# STM32_min.net
KiCad netlist of a schematic drawn in Altium Designer
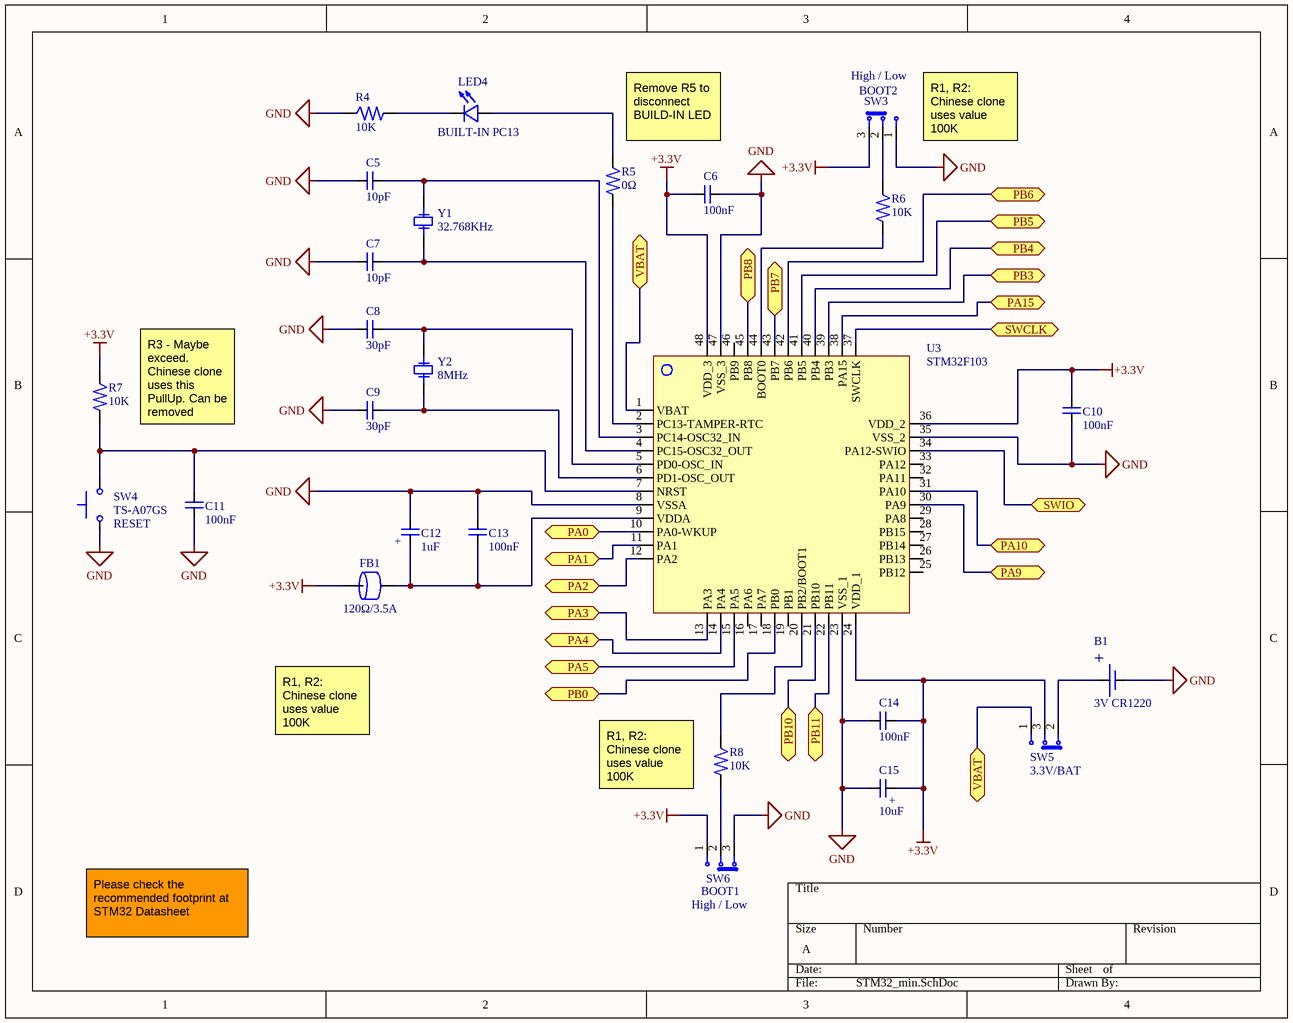
[diagram p0: STM32_min.SchDoc]

(export (version "E")
  (design (tool "Eeschema 10.0.6"))
  (components
    (comp (ref "B1")
      (value "3V CR1220")
      (footprint "THT_BH-25T-GLD")
      (description "Battery Holder for CR-2032 Type Battery BH-25T-GLD")
      (libsource (lib "THT_BH-25T-GLD") (part "THT_BH-25T-GLD"))
    )
    (comp (ref "C5")
      (value "10pF")
      (footprint "SMT_CAP_CER_MODEL_0805(2012)_SAMSUNG")
      (description "SMT SAMSUNG Ceramic Capacitor MODEL *V *pF 0805(2012) CL21C100DBANNNC(etc.)")
      (libsource (lib "SMT_CAP_CER_MODEL_0805(2012)_SAMSUNG") (part "SMT_CAP_CER_MODEL_0805(2012)_SAMSUNG"))
    )
    (comp (ref "C6")
      (value "100nF")
      (footprint "SMT_CAP_MODEL_1206(3216)_SAMSUNG")
      (description "SMT Samsung Ceramic Capacitor MODEL *V *nF 1206(3216)  CL31B104KBCNNNC(etc.)")
      (libsource (lib "SMT_CAP_MODEL_1206(3216)_SAMSUNG") (part "SMT_CAP_MODEL_1206(3216)_SAMSUNG"))
    )
    (comp (ref "C7")
      (value "10pF")
      (footprint "SMT_CAP_CER_MODEL_0805(2012)_SAMSUNG")
      (description "SMT SAMSUNG Ceramic Capacitor MODEL *V *pF 0805(2012) CL21C100DBANNNC(etc.)")
      (libsource (lib "SMT_CAP_CER_MODEL_0805(2012)_SAMSUNG") (part "SMT_CAP_CER_MODEL_0805(2012)_SAMSUNG"))
    )
    (comp (ref "C8")
      (value "30pF")
      (footprint "SMT_CAP_MODEL_1206(3216)_SAMSUNG")
      (description "SMT Samsung Ceramic Capacitor MODEL *V *nF 1206(3216)  CL31B104KBCNNNC(etc.)")
      (libsource (lib "SMT_CAP_MODEL_1206(3216)_SAMSUNG") (part "SMT_CAP_MODEL_1206(3216)_SAMSUNG"))
    )
    (comp (ref "C9")
      (value "30pF")
      (footprint "SMT_CAP_MODEL_1206(3216)_SAMSUNG")
      (description "SMT Samsung Ceramic Capacitor MODEL *V *nF 1206(3216)  CL31B104KBCNNNC(etc.)")
      (libsource (lib "SMT_CAP_MODEL_1206(3216)_SAMSUNG") (part "SMT_CAP_MODEL_1206(3216)_SAMSUNG"))
    )
    (comp (ref "C10")
      (value "100nF")
      (footprint "SMT_CAP_MODEL_1206(3216)_SAMSUNG")
      (description "SMT Samsung Ceramic Capacitor MODEL *V *nF 1206(3216)  CL31B104KBCNNNC(etc.)")
      (libsource (lib "SMT_CAP_MODEL_1206(3216)_SAMSUNG") (part "SMT_CAP_MODEL_1206(3216)_SAMSUNG"))
    )
    (comp (ref "C11")
      (value "100nF")
      (footprint "SMT_CAP_MODEL_1206(3216)_SAMSUNG")
      (description "SMT Samsung Ceramic Capacitor MODEL *V *nF 1206(3216)  CL31B104KBCNNNC(etc.)")
      (libsource (lib "SMT_CAP_MODEL_1206(3216)_SAMSUNG") (part "SMT_CAP_MODEL_1206(3216)_SAMSUNG"))
    )
    (comp (ref "C12")
      (value "1uF")
      (footprint "SMT_CAP_TANT_MODEL_1206(3216)_KYOCERA")
      (description "SMT KYOCERA Tantalum Capacitor MODEL *V *uF 1206(3216) EAN_3216-18 TAJA105M016RNJ(etc.)")
      (libsource (lib "SMT_CAP_TANT_MODEL_1206(3216)_KYOCERA") (part "SMT_CAP_TANT_MODEL_1206(3216)_KYOCERA"))
    )
    (comp (ref "C13")
      (value "100nF")
      (footprint "SMT_CAP_MODEL_1206(3216)_SAMSUNG")
      (description "SMT Samsung Ceramic Capacitor MODEL *V *nF 1206(3216)  CL31B104KBCNNNC(etc.)")
      (libsource (lib "SMT_CAP_MODEL_1206(3216)_SAMSUNG") (part "SMT_CAP_MODEL_1206(3216)_SAMSUNG"))
    )
    (comp (ref "C14")
      (value "100nF")
      (footprint "SMT_CAP_MODEL_1206(3216)_SAMSUNG")
      (description "SMT Samsung Ceramic Capacitor MODEL *V *nF 1206(3216)  CL31B104KBCNNNC(etc.)")
      (libsource (lib "SMT_CAP_MODEL_1206(3216)_SAMSUNG") (part "SMT_CAP_MODEL_1206(3216)_SAMSUNG"))
    )
    (comp (ref "C15")
      (value "10uF")
      (footprint "SMT_CAP_TANT_MODEL_1210(3528)_KYOCERA")
      (description "SMT KYOCERA Tantalum Capacitor MODEL *V *uF 1210(3528)  TAJB106K016RNJ(etc.)")
      (libsource (lib "SMT_CAP_TANT_MODEL_1210(3528)_KYOCERA") (part "SMT_CAP_TANT_MODEL_1210(3528)_KYOCERA"))
    )
    (comp (ref "FB1")
      (value "120Ω/3.5A")
      (footprint "SMT_FERR_BEAD_MODEL_1206(3216)_MURATA")
      (description "SMT MURATA Ferrite Bead MODEL 1206(3216) BLM31PG121SN1L *Ω/*mA")
      (libsource (lib "SMT_FERR_BEAD_MODEL_1206(3216)_MURATA") (part "SMT_FERR_BEAD_MODEL_1206(3216)_MURATA"))
    )
    (comp (ref "LED4")
      (value "BUILT-IN PC13")
      (footprint "DIOM2012X18N")
      (description "Led Diode 0805(2012) Cathode Mark, 20mA")
      (libsource (lib "SMT_LED_0805(2012)") (part "SMT_LED_0805(2012)"))
    )
    (comp (ref "R4")
      (value "10K")
      (footprint "SMT_RES_MODEL_1206(3216)_ROHM")
      (description "SMT ROHM Resistor MODEL 1206(3216) 1/4W MCR18ERTJ000")
      (libsource (lib "SMT_RES_MODEL_1206(3216)_ROHM") (part "SMT_RES_MODEL_1206(3216)_ROHM"))
    )
    (comp (ref "R5")
      (value "0Ω")
      (footprint "SMT_RES_MODEL_1206(3216)_ROHM")
      (description "SMT ROHM Resistor MODEL 1206(3216) 1/4W MCR18ERTJ000")
      (libsource (lib "SMT_RES_MODEL_1206(3216)_ROHM") (part "SMT_RES_MODEL_1206(3216)_ROHM"))
    )
    (comp (ref "R6")
      (value "10K")
      (footprint "SMT_RES_MODEL_1206(3216)_ROHM")
      (description "SMT ROHM Resistor MODEL 1206(3216) 1/4W MCR18ERTJ000")
      (libsource (lib "SMT_RES_MODEL_1206(3216)_ROHM") (part "SMT_RES_MODEL_1206(3216)_ROHM"))
    )
    (comp (ref "R7")
      (value "10K")
      (footprint "SMT_RES_MODEL_1206(3216)_ROHM")
      (description "SMT ROHM Resistor MODEL 1206(3216) 1/4W MCR18ERTJ000")
      (libsource (lib "SMT_RES_MODEL_1206(3216)_ROHM") (part "SMT_RES_MODEL_1206(3216)_ROHM"))
    )
    (comp (ref "R8")
      (value "10K")
      (footprint "SMT_RES_MODEL_1206(3216)_ROHM")
      (description "SMT ROHM Resistor MODEL 1206(3216) 1/4W MCR18ERTJ000")
      (libsource (lib "SMT_RES_MODEL_1206(3216)_ROHM") (part "SMT_RES_MODEL_1206(3216)_ROHM"))
    )
    (comp (ref "SW3")
      (value "BOOT2")
      (footprint "SMT_SWW_SS-B90AP_DAWNING")
      (description "Slide Switch SMD 12V 50mA 2-POS SS-B90AP-W-SP2-S085")
      (libsource (lib "") (part "SMT_SWW_SS-B90AP_DAWNING_1"))
    )
    (comp (ref "SW4")
      (value "TS-A07GS")
      (footprint "SMT_TSW-A07GS")
      (description "Tactile Switch TS-A07GS 50mA 12V")
      (libsource (lib "SMT_TSW-A07GS") (part "SMT_TSW-A07GS"))
    )
    (comp (ref "SW5")
      (value "3.3V/BAT")
      (footprint "THT_SSW_ESP1010")
      (description "Slide Switch ESP1010 12V 0.5A")
      (libsource (lib "THT_SSW_ESP1010") (part "THT_SSW_ESP1010"))
    )
    (comp (ref "SW6")
      (value "BOOT1")
      (footprint "SMT_SWW_SS-B90AP_DAWNING")
      (description "Slide Switch SMD 12V 50mA 2-POS SS-B90AP-W-SP2-S085")
      (libsource (lib "SMT_SWW_SS-B90AP_DAWNING") (part "SMT_SWW_SS-B90AP_DAWNING"))
    )
    (comp (ref "U3")
      (value "STM32F103")
      (footprint "SMT_IC_STM32F103")
      (description "MCU STM32F103x8 LQFP48 pinout")
      (libsource (lib "SMT_IC_STM32F103") (part "SMT_IC_STM32F103"))
    )
    (comp (ref "Y1")
      (value "32.768KHz")
      (footprint "SMT_XTAL_FC-135_EPSON")
      (description "SMD Quartz Crystal EPSON FC-135 12.5pF 32.768KHz ±20.0ppm")
      (libsource (lib "SMT_XTAL_FC-135_EPSON") (part "SMT_XTAL_FC-135_EPSON"))
    )
    (comp (ref "Y2")
      (value "8MHz")
      (footprint "SMT_XTAL_ATS08ASM-1E")
      (description "SMD Quartz Crystal ATS08ASM-1E 20pF 8MHz")
      (libsource (lib "SMT_XTAL_ATS08ASM-1E") (part "SMT_XTAL_ATS08ASM-1E"))
    )
  )
  (nets
    (net (code "1") (name "+3.3V") (class "Default")
      (node (ref "C10") (pin "1") (pinfunction "1_1") (pintype "passive"))
      (node (ref "C14") (pin "1") (pinfunction "1_1") (pintype "passive"))
      (node (ref "C15") (pin "1") (pinfunction "1_1") (pintype "passive"))
      (node (ref "C6") (pin "1") (pinfunction "1_1") (pintype "passive"))
      (node (ref "FB1") (pin "1") (pinfunction "1_1") (pintype "passive"))
      (node (ref "R7") (pin "2") (pinfunction "2_2") (pintype "passive"))
      (node (ref "SW3") (pin "3") (pinfunction "3_3") (pintype "passive"))
      (node (ref "SW5") (pin "3") (pinfunction "3_3") (pintype "passive"))
      (node (ref "SW6") (pin "1") (pinfunction "1_1") (pintype "passive"))
      (node (ref "U3") (pin "24") (pinfunction "VDD_1_24") (pintype "passive"))
      (node (ref "U3") (pin "36") (pinfunction "VDD_2_36") (pintype "passive"))
      (node (ref "U3") (pin "48") (pinfunction "VDD_3_48") (pintype "passive"))
    )
    (net (code "2") (name "/PA0") (class "Default")
      (node (ref "U3") (pin "10") (pinfunction "PA0-WKUP_10") (pintype "passive"))
    )
    (net (code "3") (name "/PA1") (class "Default")
      (node (ref "U3") (pin "11") (pinfunction "PA1_11") (pintype "passive"))
    )
    (net (code "4") (name "/PA2") (class "Default")
      (node (ref "U3") (pin "12") (pinfunction "PA2_12") (pintype "passive"))
    )
    (net (code "5") (name "/PA3") (class "Default")
      (node (ref "U3") (pin "13") (pinfunction "PA3_13") (pintype "passive"))
    )
    (net (code "6") (name "/PA4") (class "Default")
      (node (ref "U3") (pin "14") (pinfunction "PA4_14") (pintype "passive"))
    )
    (net (code "7") (name "/PA5") (class "Default")
      (node (ref "U3") (pin "15") (pinfunction "PA5_15") (pintype "passive"))
    )
    (net (code "8") (name "/PA9") (class "Default")
      (node (ref "U3") (pin "30") (pinfunction "PA9_30") (pintype "passive"))
    )
    (net (code "9") (name "/PA10") (class "Default")
      (node (ref "U3") (pin "31") (pinfunction "PA10_31") (pintype "passive"))
    )
    (net (code "10") (name "/PA15") (class "Default")
      (node (ref "U3") (pin "38") (pinfunction "PA15_38") (pintype "passive"))
    )
    (net (code "11") (name "/PB0") (class "Default")
      (node (ref "U3") (pin "18") (pinfunction "PB0_18") (pintype "passive"))
    )
    (net (code "12") (name "/PB3") (class "Default")
      (node (ref "U3") (pin "39") (pinfunction "PB3_39") (pintype "passive"))
    )
    (net (code "13") (name "/PB4") (class "Default")
      (node (ref "U3") (pin "40") (pinfunction "PB4_40") (pintype "passive"))
    )
    (net (code "14") (name "/PB5") (class "Default")
      (node (ref "U3") (pin "41") (pinfunction "PB5_41") (pintype "passive"))
    )
    (net (code "15") (name "/PB6") (class "Default")
      (node (ref "U3") (pin "42") (pinfunction "PB6_42") (pintype "passive"))
    )
    (net (code "16") (name "/PB7") (class "Default")
      (node (ref "U3") (pin "43") (pinfunction "PB7_43") (pintype "passive"))
    )
    (net (code "17") (name "/PB8") (class "Default")
      (node (ref "U3") (pin "45") (pinfunction "PB8_45") (pintype "passive"))
    )
    (net (code "18") (name "/PB10") (class "Default")
      (node (ref "U3") (pin "21") (pinfunction "PB10_21") (pintype "passive"))
    )
    (net (code "19") (name "/PB11") (class "Default")
      (node (ref "U3") (pin "22") (pinfunction "PB11_22") (pintype "passive"))
    )
    (net (code "20") (name "/SWCLK") (class "Default")
      (node (ref "U3") (pin "37") (pinfunction "SWCLK_37") (pintype "passive"))
    )
    (net (code "21") (name "/SWIO") (class "Default")
      (node (ref "U3") (pin "34") (pinfunction "PA12-SWIO_34") (pintype "passive"))
    )
    (net (code "22") (name "/VBAT") (class "Default")
      (node (ref "SW5") (pin "1") (pinfunction "1_1") (pintype "passive"))
      (node (ref "U3") (pin "1") (pinfunction "VBAT_1") (pintype "passive"))
    )
    (net (code "23") (name "GND") (class "Default")
      (node (ref "B1") (pin "2") (pinfunction "V-_2") (pintype "passive"))
      (node (ref "C10") (pin "2") (pinfunction "2_2") (pintype "passive"))
      (node (ref "C11") (pin "1") (pinfunction "1_1") (pintype "passive"))
      (node (ref "C12") (pin "2") (pinfunction "2_2") (pintype "passive"))
      (node (ref "C13") (pin "2") (pinfunction "2_2") (pintype "passive"))
      (node (ref "C14") (pin "2") (pinfunction "2_2") (pintype "passive"))
      (node (ref "C15") (pin "2") (pinfunction "2_2") (pintype "passive"))
      (node (ref "C5") (pin "1") (pinfunction "1_1") (pintype "passive"))
      (node (ref "C6") (pin "2") (pinfunction "2_2") (pintype "passive"))
      (node (ref "C7") (pin "1") (pinfunction "1_1") (pintype "passive"))
      (node (ref "C8") (pin "1") (pinfunction "1_1") (pintype "passive"))
      (node (ref "C9") (pin "1") (pinfunction "1_1") (pintype "passive"))
      (node (ref "R4") (pin "2") (pinfunction "2_2") (pintype "passive"))
      (node (ref "SW3") (pin "1") (pinfunction "1_1") (pintype "passive"))
      (node (ref "SW4") (pin "1") (pinfunction "1_1") (pintype "passive"))
      (node (ref "SW6") (pin "3") (pinfunction "3_3") (pintype "passive"))
      (node (ref "U3") (pin "23") (pinfunction "VSS_1_23") (pintype "passive"))
      (node (ref "U3") (pin "35") (pinfunction "VSS_2_35") (pintype "passive"))
      (node (ref "U3") (pin "47") (pinfunction "VSS_3_47") (pintype "passive"))
      (node (ref "U3") (pin "8") (pinfunction "VSSA_8") (pintype "passive"))
    )
    (net (code "24") (name "Net-(B1-V+)") (class "Default")
      (node (ref "B1") (pin "1") (pinfunction "V+_1") (pintype "passive"))
      (node (ref "SW5") (pin "2") (pinfunction "2_2") (pintype "passive"))
    )
    (net (code "25") (name "Net-(LED4-Pad1)") (class "Default")
      (node (ref "LED4") (pin "1") (pinfunction "1_1") (pintype "passive"))
      (node (ref "R5") (pin "2") (pinfunction "2_2") (pintype "passive"))
    )
    (net (code "26") (name "Net-(LED4-Pad2)") (class "Default")
      (node (ref "LED4") (pin "2") (pinfunction "2_2") (pintype "passive"))
      (node (ref "R4") (pin "1") (pinfunction "1_1") (pintype "passive"))
    )
    (net (code "27") (name "Net-(R6-Pad2)") (class "Default")
      (node (ref "R6") (pin "2") (pinfunction "2_2") (pintype "passive"))
      (node (ref "SW3") (pin "2") (pinfunction "2_2") (pintype "passive"))
    )
    (net (code "28") (name "Net-(R8-Pad1)") (class "Default")
      (node (ref "R8") (pin "1") (pinfunction "1_1") (pintype "passive"))
      (node (ref "SW6") (pin "2") (pinfunction "2_2") (pintype "passive"))
    )
    (net (code "29") (name "Net-(U3-BOOT0)") (class "Default")
      (node (ref "R6") (pin "1") (pinfunction "1_1") (pintype "passive"))
      (node (ref "U3") (pin "44") (pinfunction "BOOT0_44") (pintype "passive"))
    )
    (net (code "30") (name "Net-(U3-NRST)") (class "Default")
      (node (ref "C11") (pin "2") (pinfunction "2_2") (pintype "passive"))
      (node (ref "R7") (pin "1") (pinfunction "1_1") (pintype "passive"))
      (node (ref "SW4") (pin "2") (pinfunction "2_2") (pintype "passive"))
      (node (ref "U3") (pin "7") (pinfunction "NRST_7") (pintype "passive"))
    )
    (net (code "31") (name "Net-(U3-PB2{slash}BOOT1)") (class "Default")
      (node (ref "R8") (pin "2") (pinfunction "2_2") (pintype "passive"))
      (node (ref "U3") (pin "20") (pinfunction "PB2/BOOT1_20") (pintype "passive"))
    )
    (net (code "32") (name "Net-(U3-PC13-TAMPER-RTC)") (class "Default")
      (node (ref "R5") (pin "1") (pinfunction "1_1") (pintype "passive"))
      (node (ref "U3") (pin "2") (pinfunction "PC13-TAMPER-RTC_2") (pintype "passive"))
    )
    (net (code "33") (name "Net-(U3-PC14-OSC32_IN)") (class "Default")
      (node (ref "C5") (pin "2") (pinfunction "2_2") (pintype "passive"))
      (node (ref "U3") (pin "3") (pinfunction "PC14-OSC32_IN_3") (pintype "passive"))
      (node (ref "Y1") (pin "2") (pinfunction "2_2") (pintype "passive"))
    )
    (net (code "34") (name "Net-(U3-PC15-OSC32_OUT)") (class "Default")
      (node (ref "C7") (pin "2") (pinfunction "2_2") (pintype "passive"))
      (node (ref "U3") (pin "4") (pinfunction "PC15-OSC32_OUT_4") (pintype "passive"))
      (node (ref "Y1") (pin "1") (pinfunction "1_1") (pintype "passive"))
    )
    (net (code "35") (name "Net-(U3-PD0-OSC_IN)") (class "Default")
      (node (ref "C8") (pin "2") (pinfunction "2_2") (pintype "passive"))
      (node (ref "U3") (pin "5") (pinfunction "PD0-OSC_IN_5") (pintype "passive"))
      (node (ref "Y2") (pin "2") (pinfunction "2_2") (pintype "passive"))
    )
    (net (code "36") (name "Net-(U3-PD1-OSC_OUT)") (class "Default")
      (node (ref "C9") (pin "2") (pinfunction "2_2") (pintype "passive"))
      (node (ref "U3") (pin "6") (pinfunction "PD1-OSC_OUT_6") (pintype "passive"))
      (node (ref "Y2") (pin "1") (pinfunction "1_1") (pintype "passive"))
    )
    (net (code "37") (name "Net-(U3-VDDA)") (class "Default")
      (node (ref "C12") (pin "1") (pinfunction "1_1") (pintype "passive"))
      (node (ref "C13") (pin "1") (pinfunction "1_1") (pintype "passive"))
      (node (ref "FB1") (pin "2") (pinfunction "2_2") (pintype "passive"))
      (node (ref "U3") (pin "9") (pinfunction "VDDA_9") (pintype "passive"))
    )
    (net (code "38") (name "unconnected-(U3-PA6-Pad16)") (class "Default")
      (node (ref "U3") (pin "16") (pinfunction "PA6_16") (pintype "passive"))
    )
    (net (code "39") (name "unconnected-(U3-PA7-Pad17)") (class "Default")
      (node (ref "U3") (pin "17") (pinfunction "PA7_17") (pintype "passive"))
    )
    (net (code "40") (name "unconnected-(U3-PA8-Pad29)") (class "Default")
      (node (ref "U3") (pin "29") (pinfunction "PA8_29") (pintype "passive"))
    )
    (net (code "41") (name "unconnected-(U3-PA11-Pad32)") (class "Default")
      (node (ref "U3") (pin "32") (pinfunction "PA11_32") (pintype "passive"))
    )
    (net (code "42") (name "unconnected-(U3-PA12-Pad33)") (class "Default")
      (node (ref "U3") (pin "33") (pinfunction "PA12_33") (pintype "passive"))
    )
    (net (code "43") (name "unconnected-(U3-PB1-Pad19)") (class "Default")
      (node (ref "U3") (pin "19") (pinfunction "PB1_19") (pintype "passive"))
    )
    (net (code "44") (name "unconnected-(U3-PB9-Pad46)") (class "Default")
      (node (ref "U3") (pin "46") (pinfunction "PB9_46") (pintype "passive"))
    )
    (net (code "45") (name "unconnected-(U3-PB12-Pad25)") (class "Default")
      (node (ref "U3") (pin "25") (pinfunction "PB12_25") (pintype "passive"))
    )
    (net (code "46") (name "unconnected-(U3-PB13-Pad26)") (class "Default")
      (node (ref "U3") (pin "26") (pinfunction "PB13_26") (pintype "passive"))
    )
    (net (code "47") (name "unconnected-(U3-PB14-Pad27)") (class "Default")
      (node (ref "U3") (pin "27") (pinfunction "PB14_27") (pintype "passive"))
    )
    (net (code "48") (name "unconnected-(U3-PB15-Pad28)") (class "Default")
      (node (ref "U3") (pin "28") (pinfunction "PB15_28") (pintype "passive"))
    )
  )
)
